# KEF_Weather_Station.net
KiCad netlist of a schematic drawn in EAGLE
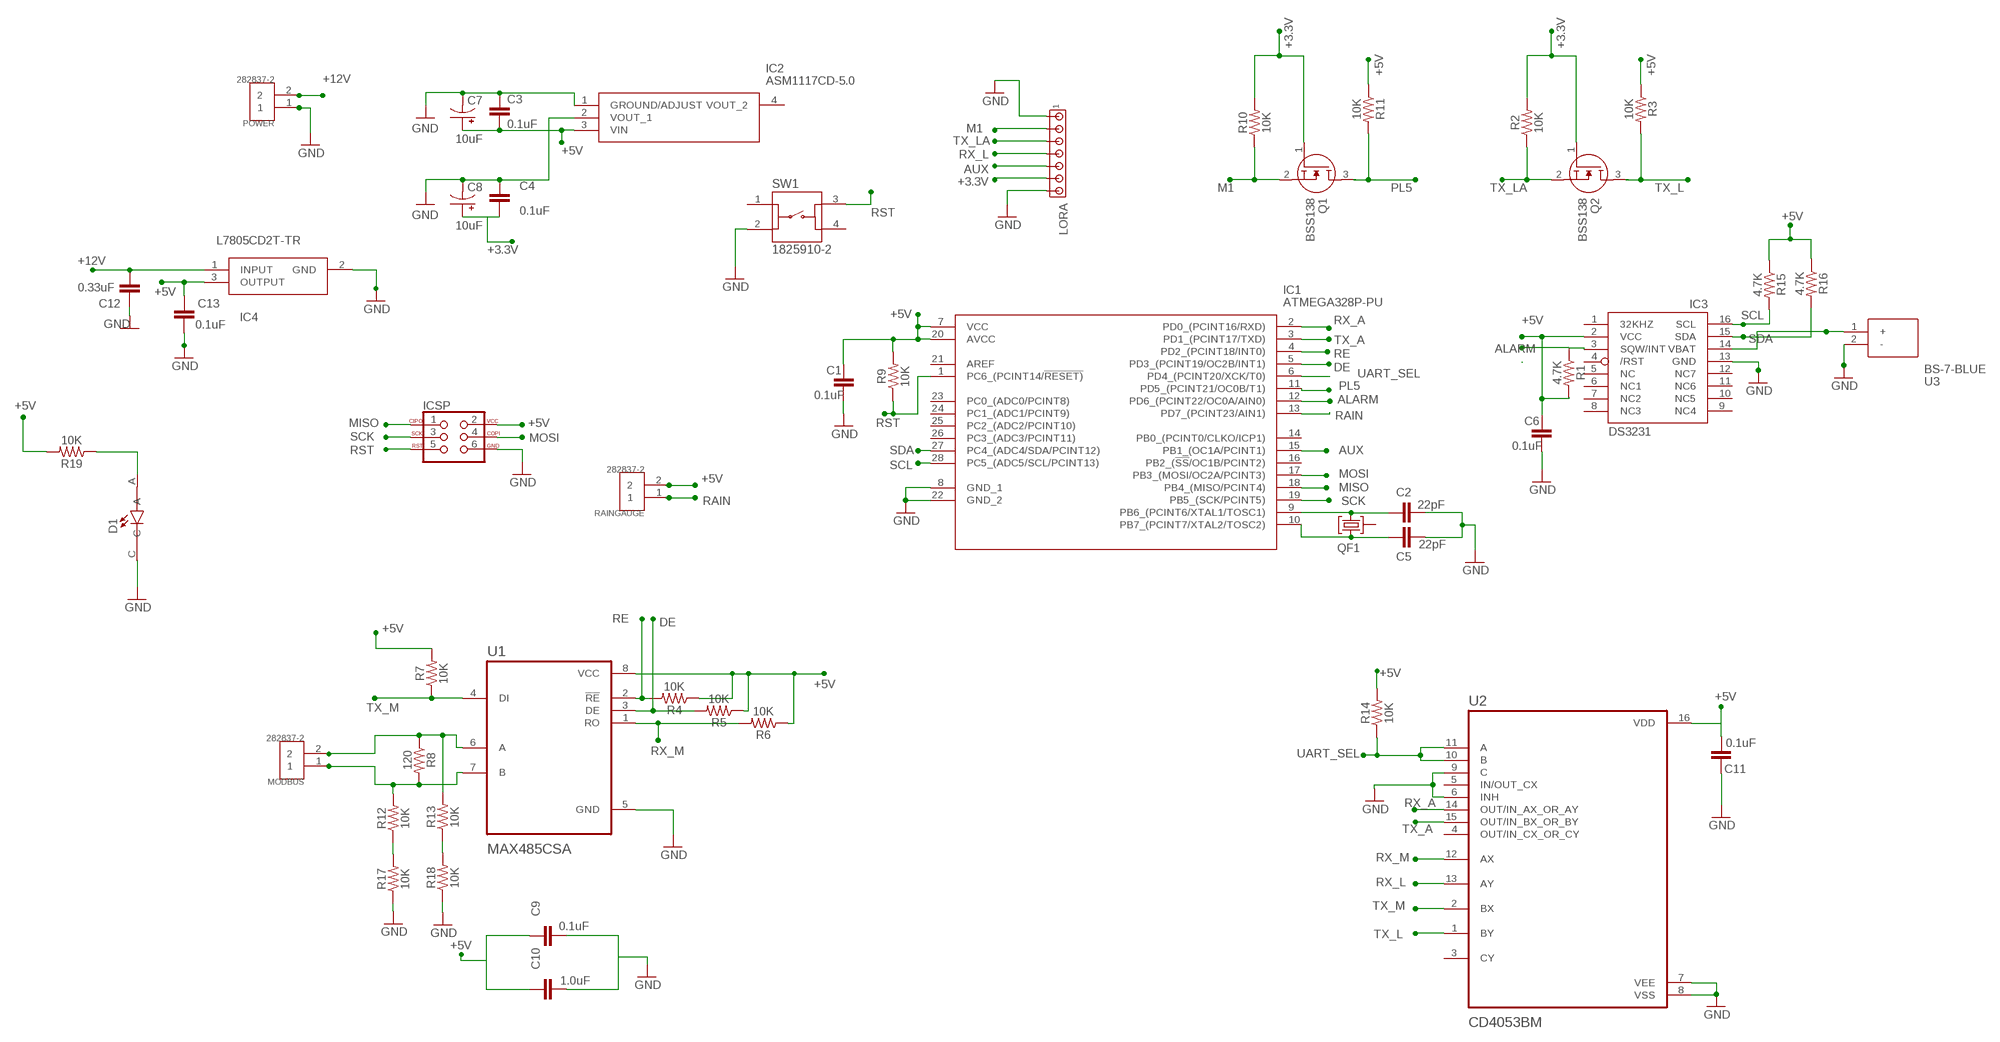
[diagram p0: schematic, sheet 1]

(export (version "E")
  (design (tool "Eeschema 10.0.6"))
  (components
    (comp (ref "C1")
      (value "0.1uF")
      (footprint "eagle-import:1206")
      (libsource (lib "eagle-import") (part "1.0UF-1206-50V-10%"))
    )
    (comp (ref "C2")
      (value "22pF")
      (footprint "eagle-import:1206")
      (libsource (lib "eagle-import") (part "1.0UF-1206-50V-10%"))
    )
    (comp (ref "C3")
      (value "0.1uF")
      (footprint "eagle-import:1206")
      (libsource (lib "eagle-import") (part "1.0UF-1206-50V-10%"))
    )
    (comp (ref "C4")
      (value "0.1uF")
      (footprint "eagle-import:1206")
      (libsource (lib "eagle-import") (part "1.0UF-1206-50V-10%"))
    )
    (comp (ref "C5")
      (value "22pF")
      (footprint "eagle-import:1206")
      (libsource (lib "eagle-import") (part "1.0UF-1206-50V-10%"))
    )
    (comp (ref "C6")
      (value "0.1uF")
      (footprint "eagle-import:1206")
      (libsource (lib "eagle-import") (part "1.0UF-1206-50V-10%"))
    )
    (comp (ref "C7")
      (value "10uF")
      (footprint "eagle-import:EIA3216")
      (libsource (lib "eagle-import") (part "10UF-POLAR-EIA3216-16V-10%(TANT)"))
    )
    (comp (ref "C8")
      (value "10uF")
      (footprint "eagle-import:EIA3216")
      (libsource (lib "eagle-import") (part "10UF-POLAR-EIA3216-16V-10%(TANT)"))
    )
    (comp (ref "C9")
      (value "0.1uF")
      (footprint "eagle-import:1206")
      (libsource (lib "eagle-import") (part "1.0UF-1206-50V-10%"))
    )
    (comp (ref "C10")
      (value "1.0uF")
      (footprint "eagle-import:1206")
      (libsource (lib "eagle-import") (part "1.0UF-1206-50V-10%"))
    )
    (comp (ref "C11")
      (value "0.1uF")
      (footprint "eagle-import:1206")
      (libsource (lib "eagle-import") (part "1.0UF-1206-50V-10%"))
    )
    (comp (ref "C12")
      (value "0.33uF")
      (footprint "eagle-import:1206")
      (libsource (lib "eagle-import") (part "1.0UF-1206-50V-10%"))
    )
    (comp (ref "C13")
      (value "0.1uF")
      (footprint "eagle-import:1206")
      (libsource (lib "eagle-import") (part "1.0UF-1206-50V-10%"))
    )
    (comp (ref "D1")
      (value "LTST-C230KFKT")
      (footprint "eagle-import:LEDC3216X110")
      (fields (field (name "MF") "Lite-On Inc."))
      (libsource (lib "eagle-import") (part "LTST-C230KFKT"))
    )
    (comp (ref "IC1")
      (value "ATMEGA328P-PU")
      (footprint "eagle-import:DIP794W53P254L3467H457Q28N")
      (fields (field (name "MOUSER_PART_NUMBER") "556-ATMEGA328P-PU"))
      (libsource (lib "eagle-import") (part "ATMEGA328P-PU"))
    )
    (comp (ref "IC2")
      (value "ASM1117CD-5.0")
      (footprint "eagle-import:SOT229P700X180-4N")
      (libsource (lib "eagle-import") (part "ASM1117CD-5.0"))
    )
    (comp (ref "IC3")
      (value "DS3231/SO")
      (footprint "eagle-import:SO16W")
      (fields (field (name "MF") "Maxim Integrated") (field (name "MP") "DS3231"))
      (libsource (lib "eagle-import") (part "DS3231/SO"))
    )
    (comp (ref "IC4")
      (value "L7805CD2T-TR")
      (footprint "eagle-import:L7805CD2T")
      (fields (field (name "MOUSER_PART_NUMBER") "511-L7805CD2T-TR"))
      (libsource (lib "eagle-import") (part "L7805CD2T-TR"))
    )
    (comp (ref "ICSP")
      (value "AVR_SPI_PROG_3X2NS")
      (footprint "eagle-import:2X3-NS")
      (libsource (lib "eagle-import") (part "AVR_SPI_PROG_3X2NS"))
    )
    (comp (ref "LORA")
      (value "MTA07-100")
      (footprint "eagle-import:10X07MTA")
      (libsource (lib "eagle-import") (part "MTA07-100"))
    )
    (comp (ref "MODBUS")
      (value "282837-2")
      (footprint "eagle-import:TE_282837-2")
      (fields (field (name "MF") "TE Connectivity"))
      (libsource (lib "eagle-import") (part "282837-2"))
    )
    (comp (ref "POWER")
      (value "282837-2")
      (footprint "eagle-import:TE_282837-2")
      (fields (field (name "MF") "TE Connectivity"))
      (libsource (lib "eagle-import") (part "282837-2"))
    )
    (comp (ref "Q1")
      (value "BSS138")
      (footprint "eagle-import:SOT95P240X120-3N")
      (fields (field (name "MOUSER_PART_NUMBER") "512-BSS138"))
      (libsource (lib "eagle-import") (part "BSS138"))
    )
    (comp (ref "Q2")
      (value "BSS138")
      (footprint "eagle-import:SOT95P240X120-3N")
      (fields (field (name "MOUSER_PART_NUMBER") "512-BSS138"))
      (libsource (lib "eagle-import") (part "BSS138"))
    )
    (comp (ref "QF1")
      (value "8M10AHC49T")
      (footprint "eagle-import:HC49U")
      (libsource (lib "eagle-import") (part "8M10AHC49T"))
    )
    (comp (ref "R1")
      (value "4.7K")
      (footprint "eagle-import:1206")
      (libsource (lib "eagle-import") (part "10OHM-1206-1/4W-1%"))
    )
    (comp (ref "R2")
      (value "10K")
      (footprint "eagle-import:1206")
      (libsource (lib "eagle-import") (part "10OHM-1206-1/4W-1%"))
    )
    (comp (ref "R3")
      (value "10K")
      (footprint "eagle-import:1206")
      (libsource (lib "eagle-import") (part "10OHM-1206-1/4W-1%"))
    )
    (comp (ref "R4")
      (value "10K")
      (footprint "eagle-import:1206")
      (libsource (lib "eagle-import") (part "10OHM-1206-1/4W-1%"))
    )
    (comp (ref "R5")
      (value "10K")
      (footprint "eagle-import:1206")
      (libsource (lib "eagle-import") (part "10OHM-1206-1/4W-1%"))
    )
    (comp (ref "R6")
      (value "10K")
      (footprint "eagle-import:1206")
      (libsource (lib "eagle-import") (part "10OHM-1206-1/4W-1%"))
    )
    (comp (ref "R7")
      (value "10K")
      (footprint "eagle-import:1206")
      (libsource (lib "eagle-import") (part "10OHM-1206-1/4W-1%"))
    )
    (comp (ref "R8")
      (value "120")
      (footprint "eagle-import:1206")
      (libsource (lib "eagle-import") (part "10OHM-1206-1/4W-1%"))
    )
    (comp (ref "R9")
      (value "10K")
      (footprint "eagle-import:1206")
      (libsource (lib "eagle-import") (part "10OHM-1206-1/4W-1%"))
    )
    (comp (ref "R10")
      (value "10K")
      (footprint "eagle-import:1206")
      (libsource (lib "eagle-import") (part "10OHM-1206-1/4W-1%"))
    )
    (comp (ref "R11")
      (value "10K")
      (footprint "eagle-import:1206")
      (libsource (lib "eagle-import") (part "10OHM-1206-1/4W-1%"))
    )
    (comp (ref "R12")
      (value "10K")
      (footprint "eagle-import:1206")
      (libsource (lib "eagle-import") (part "10OHM-1206-1/4W-1%"))
    )
    (comp (ref "R13")
      (value "10K")
      (footprint "eagle-import:1206")
      (libsource (lib "eagle-import") (part "10OHM-1206-1/4W-1%"))
    )
    (comp (ref "R14")
      (value "10K")
      (footprint "eagle-import:1206")
      (libsource (lib "eagle-import") (part "10OHM-1206-1/4W-1%"))
    )
    (comp (ref "R15")
      (value "4.7K")
      (footprint "eagle-import:1206")
      (libsource (lib "eagle-import") (part "10OHM-1206-1/4W-1%"))
    )
    (comp (ref "R16")
      (value "4.7K")
      (footprint "eagle-import:1206")
      (libsource (lib "eagle-import") (part "10OHM-1206-1/4W-1%"))
    )
    (comp (ref "R17")
      (value "10K")
      (footprint "eagle-import:1206")
      (libsource (lib "eagle-import") (part "10OHM-1206-1/4W-1%"))
    )
    (comp (ref "R18")
      (value "10K")
      (footprint "eagle-import:1206")
      (libsource (lib "eagle-import") (part "10OHM-1206-1/4W-1%"))
    )
    (comp (ref "R19")
      (value "10K")
      (footprint "eagle-import:1206")
      (libsource (lib "eagle-import") (part "10OHM-1206-1/4W-1%"))
    )
    (comp (ref "RAINGAUGE")
      (value "282837-2")
      (footprint "eagle-import:TE_282837-2")
      (fields (field (name "MF") "TE Connectivity"))
      (libsource (lib "eagle-import") (part "282837-2"))
    )
    (comp (ref "SW1")
      (value "1825910-2")
      (footprint "eagle-import:TE_1825910-2")
      (fields (field (name "MF") "TE Connectivity"))
      (libsource (lib "eagle-import") (part "1825910-2"))
    )
    (comp (ref "U1")
      (value "MAX485CSA")
      (footprint "eagle-import:SOIC127P600X175-8N")
      (fields (field (name "MF") "Maxim Integrated"))
      (libsource (lib "eagle-import") (part "MAX485CSA"))
    )
    (comp (ref "U2")
      (value "CD4053BM")
      (footprint "eagle-import:SOIC127P600X175-16N")
      (fields (field (name "MF") "Texas Instruments"))
      (libsource (lib "eagle-import") (part "CD4053BM"))
    )
    (comp (ref "U3")
      (value "BS-7-BLUE")
      (footprint "eagle-import:BS-7-BLUE_1")
      (libsource (lib "eagle-import") (part "BS-7-BLUE"))
    )
  )
  (nets
    (net (code "1") (name "/+3.3V") (class "Default")
      (node (ref "C4") (pin "2") (pinfunction "2_2") (pintype "passive"))
      (node (ref "C8") (pin "+") (pinfunction "+_+") (pintype "passive"))
      (node (ref "LORA") (pin "6") (pinfunction "6_6") (pintype "passive"))
      (node (ref "Q1") (pin "1") (pinfunction "G_1") (pintype "bidirectional"))
      (node (ref "Q2") (pin "1") (pinfunction "G_1") (pintype "bidirectional"))
      (node (ref "R10") (pin "2") (pinfunction "2_2") (pintype "passive"))
      (node (ref "R2") (pin "2") (pinfunction "2_2") (pintype "passive"))
    )
    (net (code "2") (name "/+5V") (class "Default")
      (node (ref "C1") (pin "1") (pinfunction "1_1") (pintype "passive"))
      (node (ref "C10") (pin "1") (pinfunction "1_1") (pintype "passive"))
      (node (ref "C11") (pin "2") (pinfunction "2_2") (pintype "passive"))
      (node (ref "C13") (pin "1") (pinfunction "1_1") (pintype "passive"))
      (node (ref "C3") (pin "2") (pinfunction "2_2") (pintype "passive"))
      (node (ref "C6") (pin "1") (pinfunction "1_1") (pintype "passive"))
      (node (ref "C7") (pin "+") (pinfunction "+_+") (pintype "passive"))
      (node (ref "C9") (pin "1") (pinfunction "1_1") (pintype "passive"))
      (node (ref "IC1") (pin "20") (pinfunction "AVCC_20") (pintype "bidirectional"))
      (node (ref "IC1") (pin "7") (pinfunction "VCC_7") (pintype "bidirectional"))
      (node (ref "IC2") (pin "3") (pinfunction "VIN_3") (pintype "bidirectional"))
      (node (ref "IC3") (pin "2") (pinfunction "VCC_2") (pintype "power_in"))
      (node (ref "IC4") (pin "3") (pinfunction "OUTPUT_3") (pintype "bidirectional"))
      (node (ref "ICSP") (pin "2") (pinfunction "2_2") (pintype "passive"))
      (node (ref "R1") (pin "2") (pinfunction "2_2") (pintype "passive"))
      (node (ref "R11") (pin "1") (pinfunction "1_1") (pintype "passive"))
      (node (ref "R14") (pin "2") (pinfunction "2_2") (pintype "passive"))
      (node (ref "R15") (pin "1") (pinfunction "1_1") (pintype "passive"))
      (node (ref "R16") (pin "1") (pinfunction "1_1") (pintype "passive"))
      (node (ref "R19") (pin "2") (pinfunction "2_2") (pintype "passive"))
      (node (ref "R3") (pin "1") (pinfunction "1_1") (pintype "passive"))
      (node (ref "R4") (pin "1") (pinfunction "1_1") (pintype "passive"))
      (node (ref "R5") (pin "1") (pinfunction "1_1") (pintype "passive"))
      (node (ref "R6") (pin "1") (pinfunction "1_1") (pintype "passive"))
      (node (ref "R7") (pin "2") (pinfunction "2_2") (pintype "passive"))
      (node (ref "R9") (pin "2") (pinfunction "2_2") (pintype "passive"))
      (node (ref "RAINGAUGE") (pin "2") (pinfunction "2_2") (pintype "passive"))
      (node (ref "U1") (pin "8") (pinfunction "VCC_8") (pintype "power_in"))
      (node (ref "U2") (pin "16") (pinfunction "VDD_16") (pintype "power_in"))
    )
    (net (code "3") (name "/+12V") (class "Default")
      (node (ref "C12") (pin "1") (pinfunction "1_1") (pintype "passive"))
      (node (ref "IC4") (pin "1") (pinfunction "INPUT_1") (pintype "bidirectional"))
      (node (ref "POWER") (pin "2") (pinfunction "2_2") (pintype "passive"))
    )
    (net (code "4") (name "/ALARM") (class "Default")
      (node (ref "IC1") (pin "12") (pinfunction "PD6_(PCINT22/OC0A/AIN0)_12") (pintype "bidirectional"))
      (node (ref "IC3") (pin "3") (pinfunction "SQW/INT_3") (pintype "output"))
      (node (ref "R1") (pin "1") (pinfunction "1_1") (pintype "passive"))
    )
    (net (code "5") (name "/AUX") (class "Default")
      (node (ref "IC1") (pin "15") (pinfunction "PB1_(OC1A/PCINT1)_15") (pintype "bidirectional"))
      (node (ref "LORA") (pin "5") (pinfunction "5_5") (pintype "passive"))
    )
    (net (code "6") (name "/DE") (class "Default")
      (node (ref "IC1") (pin "5") (pinfunction "PD3_(PCINT19/OC2B/INT1)_5") (pintype "bidirectional"))
      (node (ref "R5") (pin "2") (pinfunction "2_2") (pintype "passive"))
      (node (ref "U1") (pin "3") (pinfunction "DE_3") (pintype "output"))
    )
    (net (code "7") (name "/M1") (class "Default")
      (node (ref "LORA") (pin "2") (pinfunction "2_2") (pintype "passive"))
      (node (ref "Q1") (pin "2") (pinfunction "S_2") (pintype "bidirectional"))
      (node (ref "R10") (pin "1") (pinfunction "1_1") (pintype "passive"))
    )
    (net (code "8") (name "/MISO") (class "Default")
      (node (ref "IC1") (pin "18") (pinfunction "PB4_(MISO/PCINT4)_18") (pintype "bidirectional"))
      (node (ref "ICSP") (pin "1") (pinfunction "1_1") (pintype "passive"))
    )
    (net (code "9") (name "/MOSI") (class "Default")
      (node (ref "IC1") (pin "17") (pinfunction "PB3_(MOSI/OC2A/PCINT3)_17") (pintype "bidirectional"))
      (node (ref "ICSP") (pin "4") (pinfunction "4_4") (pintype "passive"))
    )
    (net (code "10") (name "/PL5") (class "Default")
      (node (ref "IC1") (pin "11") (pinfunction "PD5_(PCINT21/OC0B/T1)_11") (pintype "bidirectional"))
      (node (ref "Q1") (pin "3") (pinfunction "D_3") (pintype "bidirectional"))
      (node (ref "R11") (pin "2") (pinfunction "2_2") (pintype "passive"))
    )
    (net (code "11") (name "/RAIN") (class "Default")
      (node (ref "IC1") (pin "13") (pinfunction "PD7_(PCINT23/AIN1)_13") (pintype "bidirectional"))
      (node (ref "RAINGAUGE") (pin "1") (pinfunction "1_1") (pintype "passive"))
    )
    (net (code "12") (name "/RE") (class "Default")
      (node (ref "IC1") (pin "4") (pinfunction "PD2_(PCINT18/INT0)_4") (pintype "bidirectional"))
      (node (ref "R4") (pin "2") (pinfunction "2_2") (pintype "passive"))
      (node (ref "U1") (pin "2") (pinfunction "~{RE}_2") (pintype "output"))
    )
    (net (code "13") (name "/RST") (class "Default")
      (node (ref "IC1") (pin "1") (pinfunction "PC6_(PCINT14/~{RESET})_1") (pintype "bidirectional"))
      (node (ref "ICSP") (pin "5") (pinfunction "5_5") (pintype "passive"))
      (node (ref "R9") (pin "1") (pinfunction "1_1") (pintype "passive"))
      (node (ref "SW1") (pin "3") (pinfunction "3_3") (pintype "passive"))
    )
    (net (code "14") (name "/RX_A") (class "Default")
      (node (ref "IC1") (pin "2") (pinfunction "PD0_(PCINT16/RXD)_2") (pintype "bidirectional"))
      (node (ref "U2") (pin "14") (pinfunction "OUT/IN_AX_OR_AY_14") (pintype "input"))
    )
    (net (code "15") (name "/RX_L") (class "Default")
      (node (ref "LORA") (pin "4") (pinfunction "4_4") (pintype "passive"))
      (node (ref "U2") (pin "13") (pinfunction "AY_13") (pintype "bidirectional"))
    )
    (net (code "16") (name "/RX_M") (class "Default")
      (node (ref "R6") (pin "2") (pinfunction "2_2") (pintype "passive"))
      (node (ref "U1") (pin "1") (pinfunction "RO_1") (pintype "output"))
      (node (ref "U2") (pin "12") (pinfunction "AX_12") (pintype "bidirectional"))
    )
    (net (code "17") (name "/SCK") (class "Default")
      (node (ref "IC1") (pin "19") (pinfunction "PB5_(SCK/PCINT5)_19") (pintype "bidirectional"))
      (node (ref "ICSP") (pin "3") (pinfunction "3_3") (pintype "passive"))
    )
    (net (code "18") (name "/SCL") (class "Default")
      (node (ref "IC1") (pin "28") (pinfunction "PC5_(ADC5/SCL/PCINT13)_28") (pintype "bidirectional"))
      (node (ref "IC3") (pin "16") (pinfunction "SCL_16") (pintype "bidirectional"))
      (node (ref "R15") (pin "2") (pinfunction "2_2") (pintype "passive"))
    )
    (net (code "19") (name "/SDA") (class "Default")
      (node (ref "IC1") (pin "27") (pinfunction "PC4_(ADC4/SDA/PCINT12)_27") (pintype "bidirectional"))
      (node (ref "IC3") (pin "15") (pinfunction "SDA_15") (pintype "bidirectional"))
      (node (ref "R16") (pin "2") (pinfunction "2_2") (pintype "passive"))
    )
    (net (code "20") (name "/TX_A") (class "Default")
      (node (ref "IC1") (pin "3") (pinfunction "PD1_(PCINT17/TXD)_3") (pintype "bidirectional"))
      (node (ref "U2") (pin "15") (pinfunction "OUT/IN_BX_OR_BY_15") (pintype "input"))
    )
    (net (code "21") (name "/TX_L") (class "Default")
      (node (ref "Q2") (pin "3") (pinfunction "D_3") (pintype "bidirectional"))
      (node (ref "R3") (pin "2") (pinfunction "2_2") (pintype "passive"))
      (node (ref "U2") (pin "1") (pinfunction "BY_1") (pintype "bidirectional"))
    )
    (net (code "22") (name "/TX_LA") (class "Default")
      (node (ref "LORA") (pin "3") (pinfunction "3_3") (pintype "passive"))
      (node (ref "Q2") (pin "2") (pinfunction "S_2") (pintype "bidirectional"))
      (node (ref "R2") (pin "1") (pinfunction "1_1") (pintype "passive"))
    )
    (net (code "23") (name "/TX_M") (class "Default")
      (node (ref "R7") (pin "1") (pinfunction "1_1") (pintype "passive"))
      (node (ref "U1") (pin "4") (pinfunction "DI_4") (pintype "input"))
      (node (ref "U2") (pin "2") (pinfunction "BX_2") (pintype "bidirectional"))
    )
    (net (code "24") (name "/UART_SEL") (class "Default")
      (node (ref "IC1") (pin "6") (pinfunction "PD4_(PCINT20/XCK/T0)_6") (pintype "bidirectional"))
      (node (ref "R14") (pin "1") (pinfunction "1_1") (pintype "passive"))
      (node (ref "U2") (pin "10") (pinfunction "B_10") (pintype "input"))
      (node (ref "U2") (pin "11") (pinfunction "A_11") (pintype "input"))
    )
    (net (code "25") (name "GND") (class "Default")
      (node (ref "C1") (pin "2") (pinfunction "2_2") (pintype "passive"))
      (node (ref "C10") (pin "2") (pinfunction "2_2") (pintype "passive"))
      (node (ref "C11") (pin "1") (pinfunction "1_1") (pintype "passive"))
      (node (ref "C12") (pin "2") (pinfunction "2_2") (pintype "passive"))
      (node (ref "C13") (pin "2") (pinfunction "2_2") (pintype "passive"))
      (node (ref "C2") (pin "2") (pinfunction "2_2") (pintype "passive"))
      (node (ref "C3") (pin "1") (pinfunction "1_1") (pintype "passive"))
      (node (ref "C4") (pin "1") (pinfunction "1_1") (pintype "passive"))
      (node (ref "C5") (pin "2") (pinfunction "2_2") (pintype "passive"))
      (node (ref "C6") (pin "2") (pinfunction "2_2") (pintype "passive"))
      (node (ref "C7") (pin "-") (pinfunction "-_-") (pintype "passive"))
      (node (ref "C8") (pin "-") (pinfunction "-_-") (pintype "passive"))
      (node (ref "C9") (pin "2") (pinfunction "2_2") (pintype "passive"))
      (node (ref "D1") (pin "C") (pinfunction "C_C") (pintype "passive"))
      (node (ref "IC1") (pin "22") (pinfunction "GND_2_22") (pintype "bidirectional"))
      (node (ref "IC1") (pin "8") (pinfunction "GND_1_8") (pintype "bidirectional"))
      (node (ref "IC2") (pin "1") (pinfunction "GROUND/ADJUST_1") (pintype "bidirectional"))
      (node (ref "IC2") (pin "2") (pinfunction "VOUT_1_2") (pintype "bidirectional"))
      (node (ref "IC3") (pin "13") (pinfunction "GND_13") (pintype "power_in"))
      (node (ref "IC4") (pin "2") (pinfunction "GND_2") (pintype "bidirectional"))
      (node (ref "ICSP") (pin "6") (pinfunction "6_6") (pintype "passive"))
      (node (ref "LORA") (pin "1") (pinfunction "1_1") (pintype "passive"))
      (node (ref "LORA") (pin "7") (pinfunction "7_7") (pintype "passive"))
      (node (ref "POWER") (pin "1") (pinfunction "1_1") (pintype "passive"))
      (node (ref "R17") (pin "1") (pinfunction "1_1") (pintype "passive"))
      (node (ref "R18") (pin "1") (pinfunction "1_1") (pintype "passive"))
      (node (ref "SW1") (pin "2") (pinfunction "2_2") (pintype "passive"))
      (node (ref "U1") (pin "5") (pinfunction "GND_5") (pintype "power_in"))
      (node (ref "U2") (pin "6") (pinfunction "INH_6") (pintype "input"))
      (node (ref "U2") (pin "7") (pinfunction "VEE_7") (pintype "power_in"))
      (node (ref "U2") (pin "8") (pinfunction "VSS_8") (pintype "power_in"))
      (node (ref "U2") (pin "9") (pinfunction "C_9") (pintype "input"))
      (node (ref "U3") (pin "2") (pinfunction "-_2") (pintype "bidirectional"))
    )
    (net (code "26") (name "Net-(D1-PadA)") (class "Default")
      (node (ref "D1") (pin "A") (pinfunction "A_A") (pintype "passive"))
      (node (ref "R19") (pin "1") (pinfunction "1_1") (pintype "passive"))
    )
    (net (code "27") (name "Net-(IC1-PB6_(PCINT6{slash}XTAL1{slash}TOSC1))") (class "Default")
      (node (ref "C2") (pin "1") (pinfunction "1_1") (pintype "passive"))
      (node (ref "IC1") (pin "9") (pinfunction "PB6_(PCINT6/XTAL1/TOSC1)_9") (pintype "bidirectional"))
      (node (ref "QF1") (pin "3") (pinfunction "3_3") (pintype "passive"))
    )
    (net (code "28") (name "Net-(IC1-PB7_(PCINT7{slash}XTAL2{slash}TOSC2))") (class "Default")
      (node (ref "C5") (pin "1") (pinfunction "1_1") (pintype "passive"))
      (node (ref "IC1") (pin "10") (pinfunction "PB7_(PCINT7/XTAL2/TOSC2)_10") (pintype "bidirectional"))
      (node (ref "QF1") (pin "1") (pinfunction "1_1") (pintype "passive"))
    )
    (net (code "29") (name "Net-(IC3-VBAT)") (class "Default")
      (node (ref "IC3") (pin "14") (pinfunction "VBAT_14") (pintype "power_in"))
      (node (ref "U3") (pin "1") (pinfunction "+_1") (pintype "bidirectional"))
    )
    (net (code "30") (name "Net-(R12-Pad1)") (class "Default")
      (node (ref "R12") (pin "1") (pinfunction "1_1") (pintype "passive"))
      (node (ref "R17") (pin "2") (pinfunction "2_2") (pintype "passive"))
    )
    (net (code "31") (name "Net-(R13-Pad1)") (class "Default")
      (node (ref "R13") (pin "1") (pinfunction "1_1") (pintype "passive"))
      (node (ref "R18") (pin "2") (pinfunction "2_2") (pintype "passive"))
    )
    (net (code "32") (name "Net-(U1-A)") (class "Default")
      (node (ref "MODBUS") (pin "2") (pinfunction "2_2") (pintype "passive"))
      (node (ref "R13") (pin "2") (pinfunction "2_2") (pintype "passive"))
      (node (ref "R8") (pin "1") (pinfunction "1_1") (pintype "passive"))
      (node (ref "U1") (pin "6") (pinfunction "A_6") (pintype "bidirectional"))
    )
    (net (code "33") (name "Net-(U1-B)") (class "Default")
      (node (ref "MODBUS") (pin "1") (pinfunction "1_1") (pintype "passive"))
      (node (ref "R12") (pin "2") (pinfunction "2_2") (pintype "passive"))
      (node (ref "R8") (pin "2") (pinfunction "2_2") (pintype "passive"))
      (node (ref "U1") (pin "7") (pinfunction "B_7") (pintype "bidirectional"))
    )
    (net (code "34") (name "unconnected-(IC1-AREF-Pad21)") (class "Default")
      (node (ref "IC1") (pin "21") (pinfunction "AREF_21") (pintype "bidirectional"))
    )
    (net (code "35") (name "unconnected-(IC1-PB0_(PCINT0{slash}CLKO{slash}ICP1)-Pad14)") (class "Default")
      (node (ref "IC1") (pin "14") (pinfunction "PB0_(PCINT0/CLKO/ICP1)_14") (pintype "bidirectional"))
    )
    (net (code "36") (name "unconnected-(IC1-PB2_(~{SS}{slash}OC1B{slash}PCINT2)-Pad16)") (class "Default")
      (node (ref "IC1") (pin "16") (pinfunction "PB2_(~{SS}/OC1B/PCINT2)_16") (pintype "bidirectional"))
    )
    (net (code "37") (name "unconnected-(IC1-PC0_(ADC0{slash}PCINT8)-Pad23)") (class "Default")
      (node (ref "IC1") (pin "23") (pinfunction "PC0_(ADC0/PCINT8)_23") (pintype "bidirectional"))
    )
    (net (code "38") (name "unconnected-(IC1-PC1_(ADC1{slash}PCINT9)-Pad24)") (class "Default")
      (node (ref "IC1") (pin "24") (pinfunction "PC1_(ADC1/PCINT9)_24") (pintype "bidirectional"))
    )
    (net (code "39") (name "unconnected-(IC1-PC2_(ADC2{slash}PCINT10)-Pad25)") (class "Default")
      (node (ref "IC1") (pin "25") (pinfunction "PC2_(ADC2/PCINT10)_25") (pintype "bidirectional"))
    )
    (net (code "40") (name "unconnected-(IC1-PC3_(ADC3{slash}PCINT11)-Pad26)") (class "Default")
      (node (ref "IC1") (pin "26") (pinfunction "PC3_(ADC3/PCINT11)_26") (pintype "bidirectional"))
    )
    (net (code "41") (name "unconnected-(IC2-VOUT_2-Pad4)") (class "Default")
      (node (ref "IC2") (pin "4") (pinfunction "VOUT_2_4") (pintype "bidirectional"))
    )
    (net (code "42") (name "unconnected-(IC3-32KHZ-Pad1)") (class "Default")
      (node (ref "IC3") (pin "1") (pinfunction "32KHZ_1") (pintype "output"))
    )
    (net (code "43") (name "unconnected-(IC3-NC-Pad5)") (class "Default")
      (node (ref "IC3") (pin "5") (pinfunction "NC_5") (pintype "no_connect"))
    )
    (net (code "44") (name "unconnected-(IC3-NC1-Pad6)") (class "Default")
      (node (ref "IC3") (pin "6") (pinfunction "NC1_6") (pintype "no_connect"))
    )
    (net (code "45") (name "unconnected-(IC3-NC2-Pad7)") (class "Default")
      (node (ref "IC3") (pin "7") (pinfunction "NC2_7") (pintype "no_connect"))
    )
    (net (code "46") (name "unconnected-(IC3-NC3-Pad8)") (class "Default")
      (node (ref "IC3") (pin "8") (pinfunction "NC3_8") (pintype "no_connect"))
    )
    (net (code "47") (name "unconnected-(IC3-NC4-Pad9)") (class "Default")
      (node (ref "IC3") (pin "9") (pinfunction "NC4_9") (pintype "no_connect"))
    )
    (net (code "48") (name "unconnected-(IC3-NC5-Pad10)") (class "Default")
      (node (ref "IC3") (pin "10") (pinfunction "NC5_10") (pintype "no_connect"))
    )
    (net (code "49") (name "unconnected-(IC3-NC6-Pad11)") (class "Default")
      (node (ref "IC3") (pin "11") (pinfunction "NC6_11") (pintype "no_connect"))
    )
    (net (code "50") (name "unconnected-(IC3-NC7-Pad12)") (class "Default")
      (node (ref "IC3") (pin "12") (pinfunction "NC7_12") (pintype "no_connect"))
    )
    (net (code "51") (name "unconnected-(IC3-{slash}RST-Pad4)") (class "Default")
      (node (ref "IC3") (pin "4") (pinfunction "/RST_4") (pintype "passive"))
    )
    (net (code "52") (name "unconnected-(QF1-Pad2)") (class "Default")
      (node (ref "QF1") (pin "2") (pinfunction "2_2") (pintype "passive"))
    )
    (net (code "53") (name "unconnected-(SW1-Pad1)") (class "Default")
      (node (ref "SW1") (pin "1") (pinfunction "1_1") (pintype "passive"))
    )
    (net (code "54") (name "unconnected-(SW1-Pad4)") (class "Default")
      (node (ref "SW1") (pin "4") (pinfunction "4_4") (pintype "passive"))
    )
    (net (code "55") (name "unconnected-(U2-CY-Pad3)") (class "Default")
      (node (ref "U2") (pin "3") (pinfunction "CY_3") (pintype "bidirectional"))
    )
    (net (code "56") (name "unconnected-(U2-IN{slash}OUT_CX-Pad5)") (class "Default")
      (node (ref "U2") (pin "5") (pinfunction "IN/OUT_CX_5") (pintype "input"))
    )
    (net (code "57") (name "unconnected-(U2-OUT{slash}IN_CX_OR_CY-Pad4)") (class "Default")
      (node (ref "U2") (pin "4") (pinfunction "OUT/IN_CX_OR_CY_4") (pintype "input"))
    )
  )
)
